# AD_3.net
KiCad netlist of a schematic drawn in Altium Designer
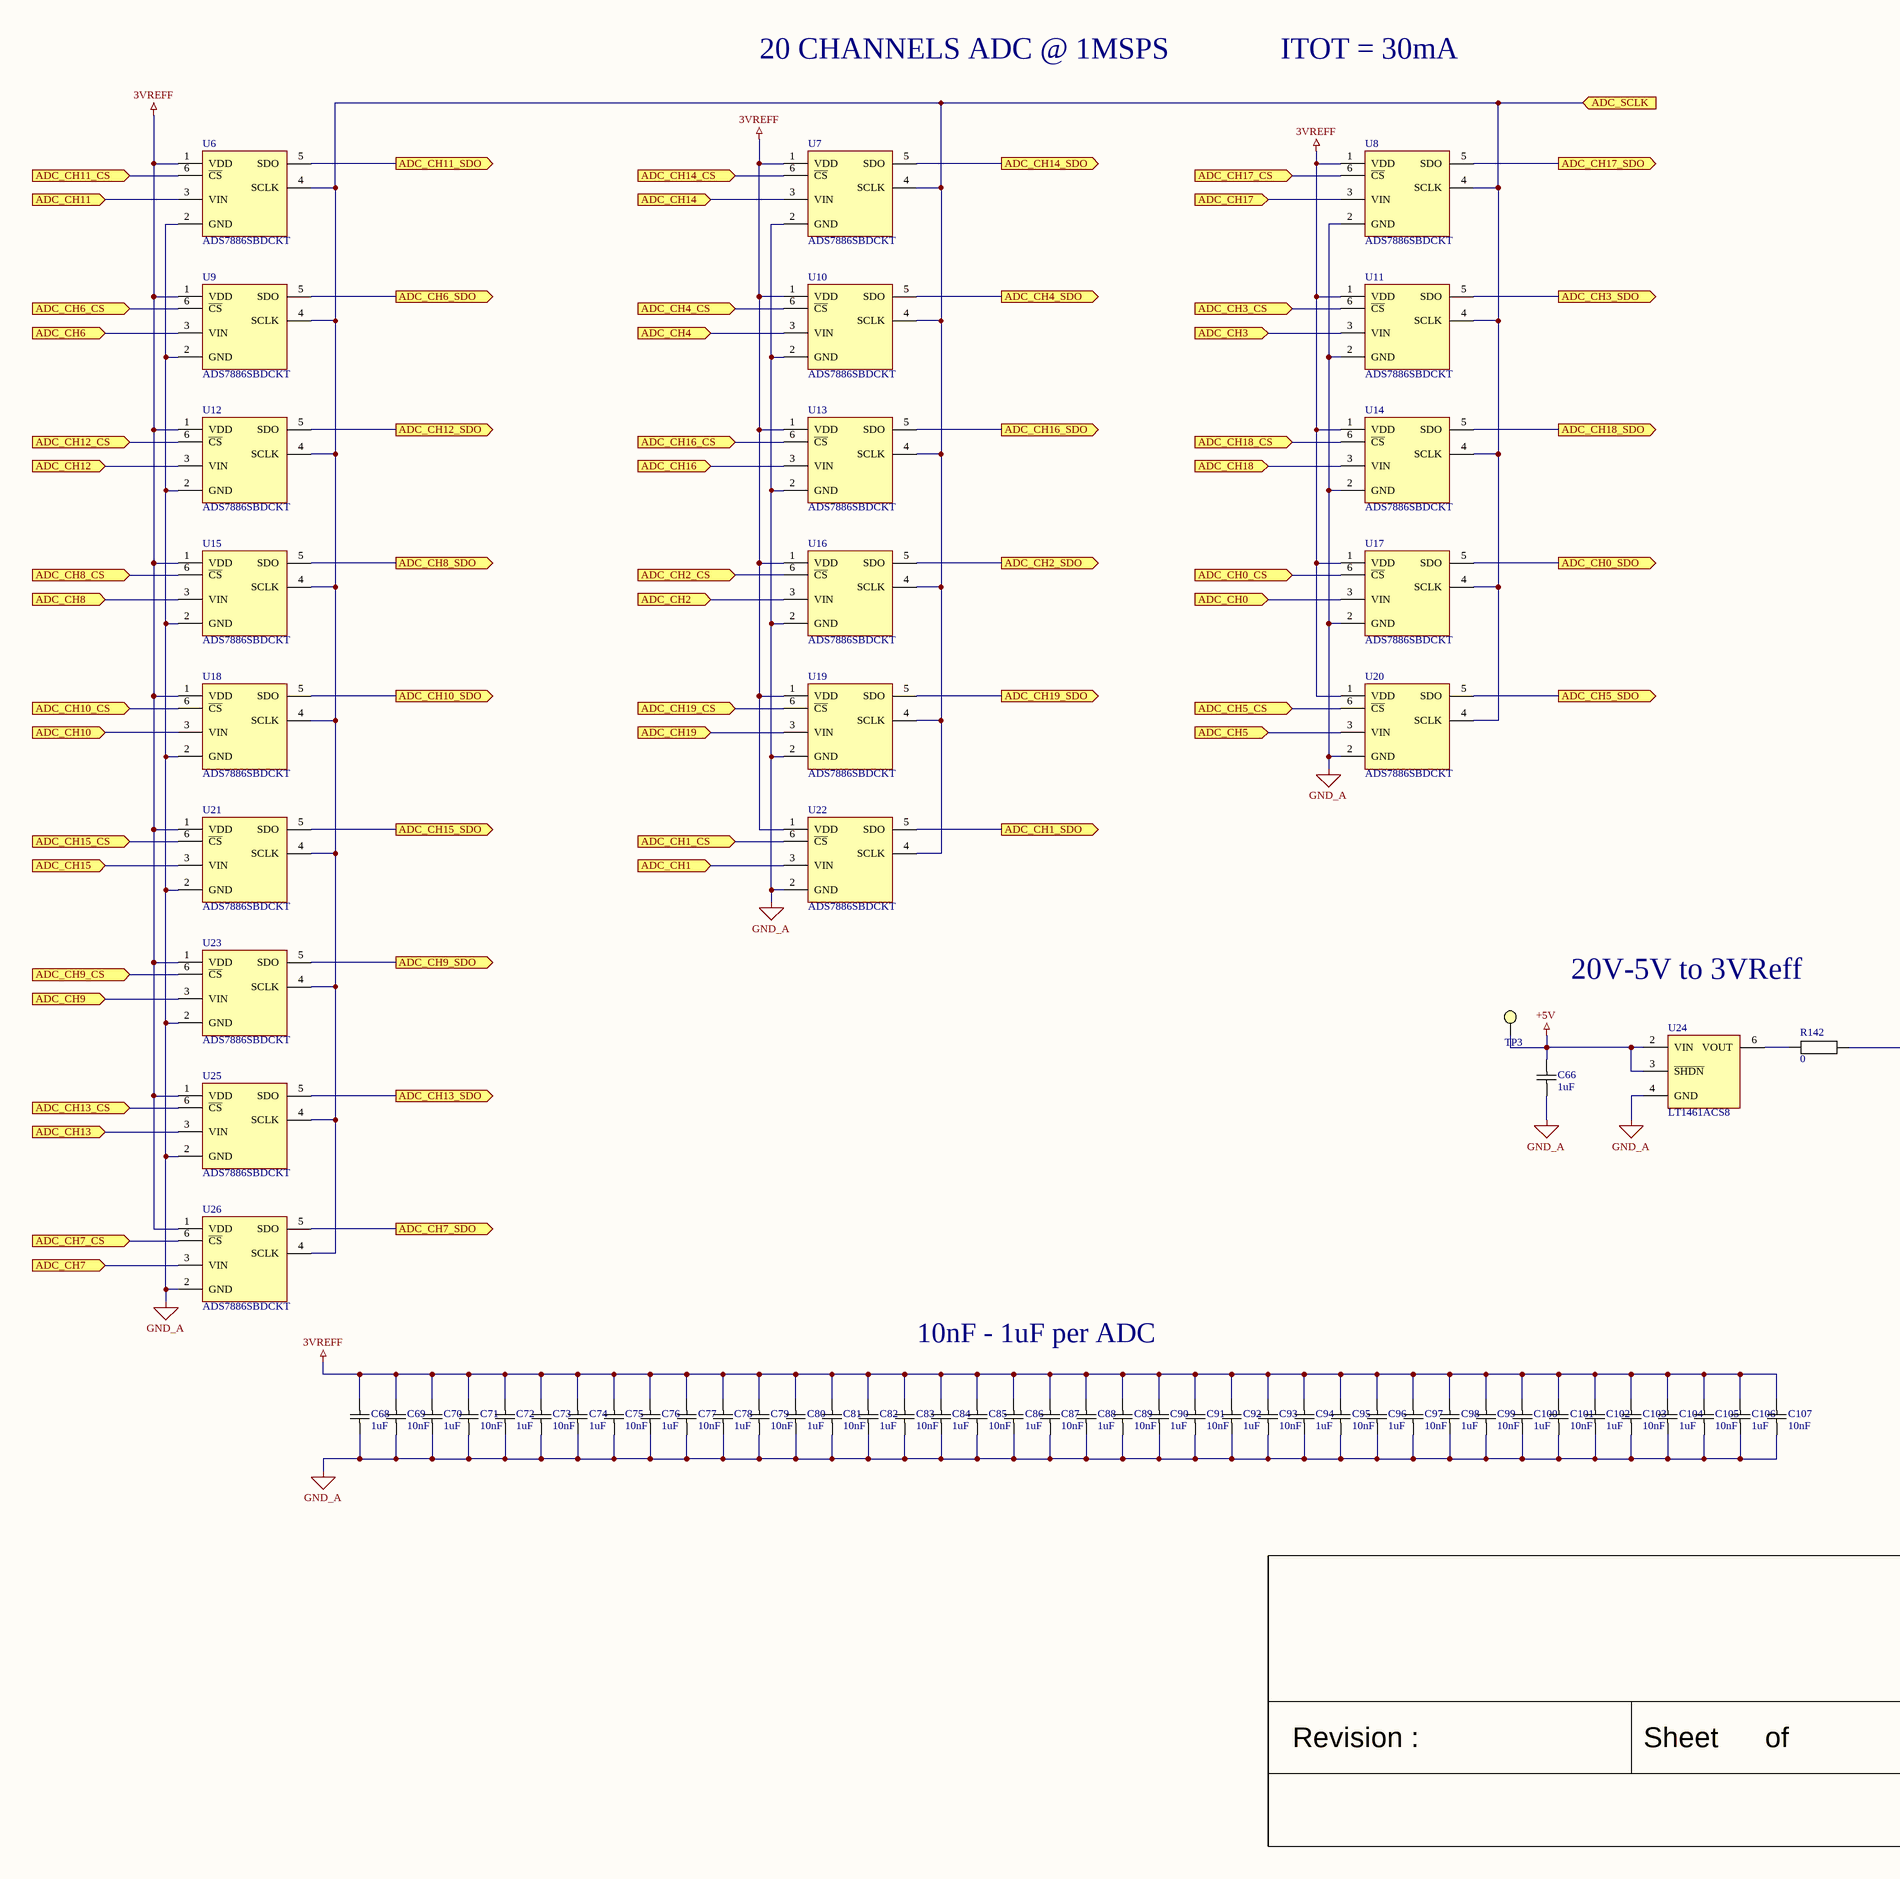
[diagram p0: AD_3.SchDoc, left]
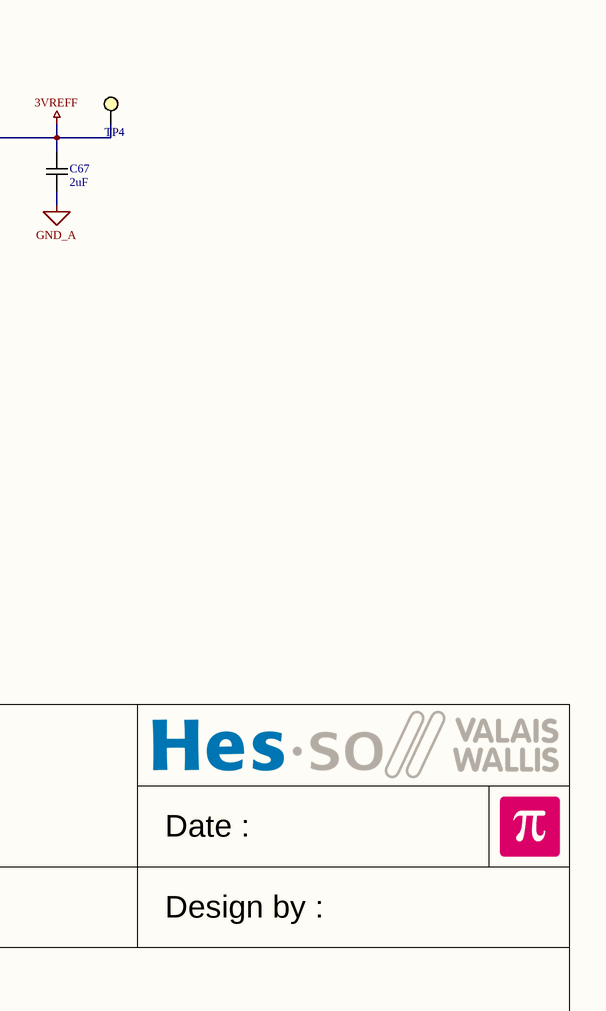
[diagram p1: AD_3.SchDoc, right]

(export (version "E")
  (design (tool "Eeschema 10.0.6"))
  (components
    (comp (ref "C66")
      (value "1uF")
      (footprint "CAPACITOR 1608 REFLOW")
      (description "Capacitor")
      (libsource (lib "Capacitor") (part "Capacitor"))
    )
    (comp (ref "C67")
      (value "2uF")
      (footprint "CAPACITOR 1608 REFLOW")
      (description "Capacitor")
      (libsource (lib "Capacitor") (part "Capacitor"))
    )
    (comp (ref "C68")
      (value "1uF")
      (footprint "CAPACITOR 1608 REFLOW")
      (description "Capacitor")
      (libsource (lib "Capacitor") (part "Capacitor"))
    )
    (comp (ref "C69")
      (value "10nF")
      (footprint "CAPACITOR 1608 REFLOW")
      (description "Capacitor")
      (libsource (lib "Capacitor") (part "Capacitor"))
    )
    (comp (ref "C70")
      (value "1uF")
      (footprint "CAPACITOR 1608 REFLOW")
      (description "Capacitor")
      (libsource (lib "Capacitor") (part "Capacitor"))
    )
    (comp (ref "C71")
      (value "10nF")
      (footprint "CAPACITOR 1608 REFLOW")
      (description "Capacitor")
      (libsource (lib "Capacitor") (part "Capacitor"))
    )
    (comp (ref "C72")
      (value "1uF")
      (footprint "CAPACITOR 1608 REFLOW")
      (description "Capacitor")
      (libsource (lib "Capacitor") (part "Capacitor"))
    )
    (comp (ref "C73")
      (value "10nF")
      (footprint "CAPACITOR 1608 REFLOW")
      (description "Capacitor")
      (libsource (lib "Capacitor") (part "Capacitor"))
    )
    (comp (ref "C74")
      (value "1uF")
      (footprint "CAPACITOR 1608 REFLOW")
      (description "Capacitor")
      (libsource (lib "Capacitor") (part "Capacitor"))
    )
    (comp (ref "C75")
      (value "10nF")
      (footprint "CAPACITOR 1608 REFLOW")
      (description "Capacitor")
      (libsource (lib "Capacitor") (part "Capacitor"))
    )
    (comp (ref "C76")
      (value "1uF")
      (footprint "CAPACITOR 1608 REFLOW")
      (description "Capacitor")
      (libsource (lib "Capacitor") (part "Capacitor"))
    )
    (comp (ref "C77")
      (value "10nF")
      (footprint "CAPACITOR 1608 REFLOW")
      (description "Capacitor")
      (libsource (lib "Capacitor") (part "Capacitor"))
    )
    (comp (ref "C78")
      (value "1uF")
      (footprint "CAPACITOR 1608 REFLOW")
      (description "Capacitor")
      (libsource (lib "Capacitor") (part "Capacitor"))
    )
    (comp (ref "C79")
      (value "10nF")
      (footprint "CAPACITOR 1608 REFLOW")
      (description "Capacitor")
      (libsource (lib "Capacitor") (part "Capacitor"))
    )
    (comp (ref "C80")
      (value "1uF")
      (footprint "CAPACITOR 1608 REFLOW")
      (description "Capacitor")
      (libsource (lib "Capacitor") (part "Capacitor"))
    )
    (comp (ref "C81")
      (value "10nF")
      (footprint "CAPACITOR 1608 REFLOW")
      (description "Capacitor")
      (libsource (lib "Capacitor") (part "Capacitor"))
    )
    (comp (ref "C82")
      (value "1uF")
      (footprint "CAPACITOR 1608 REFLOW")
      (description "Capacitor")
      (libsource (lib "Capacitor") (part "Capacitor"))
    )
    (comp (ref "C83")
      (value "10nF")
      (footprint "CAPACITOR 1608 REFLOW")
      (description "Capacitor")
      (libsource (lib "Capacitor") (part "Capacitor"))
    )
    (comp (ref "C84")
      (value "1uF")
      (footprint "CAPACITOR 1608 REFLOW")
      (description "Capacitor")
      (libsource (lib "Capacitor") (part "Capacitor"))
    )
    (comp (ref "C85")
      (value "10nF")
      (footprint "CAPACITOR 1608 REFLOW")
      (description "Capacitor")
      (libsource (lib "Capacitor") (part "Capacitor"))
    )
    (comp (ref "C86")
      (value "1uF")
      (footprint "CAPACITOR 1608 REFLOW")
      (description "Capacitor")
      (libsource (lib "Capacitor") (part "Capacitor"))
    )
    (comp (ref "C87")
      (value "10nF")
      (footprint "CAPACITOR 1608 REFLOW")
      (description "Capacitor")
      (libsource (lib "Capacitor") (part "Capacitor"))
    )
    (comp (ref "C88")
      (value "1uF")
      (footprint "CAPACITOR 1608 REFLOW")
      (description "Capacitor")
      (libsource (lib "Capacitor") (part "Capacitor"))
    )
    (comp (ref "C89")
      (value "10nF")
      (footprint "CAPACITOR 1608 REFLOW")
      (description "Capacitor")
      (libsource (lib "Capacitor") (part "Capacitor"))
    )
    (comp (ref "C90")
      (value "1uF")
      (footprint "CAPACITOR 1608 REFLOW")
      (description "Capacitor")
      (libsource (lib "Capacitor") (part "Capacitor"))
    )
    (comp (ref "C91")
      (value "10nF")
      (footprint "CAPACITOR 1608 REFLOW")
      (description "Capacitor")
      (libsource (lib "Capacitor") (part "Capacitor"))
    )
    (comp (ref "C92")
      (value "1uF")
      (footprint "CAPACITOR 1608 REFLOW")
      (description "Capacitor")
      (libsource (lib "Capacitor") (part "Capacitor"))
    )
    (comp (ref "C93")
      (value "10nF")
      (footprint "CAPACITOR 1608 REFLOW")
      (description "Capacitor")
      (libsource (lib "Capacitor") (part "Capacitor"))
    )
    (comp (ref "C94")
      (value "1uF")
      (footprint "CAPACITOR 1608 REFLOW")
      (description "Capacitor")
      (libsource (lib "Capacitor") (part "Capacitor"))
    )
    (comp (ref "C95")
      (value "10nF")
      (footprint "CAPACITOR 1608 REFLOW")
      (description "Capacitor")
      (libsource (lib "Capacitor") (part "Capacitor"))
    )
    (comp (ref "C96")
      (value "1uF")
      (footprint "CAPACITOR 1608 REFLOW")
      (description "Capacitor")
      (libsource (lib "Capacitor") (part "Capacitor"))
    )
    (comp (ref "C97")
      (value "10nF")
      (footprint "CAPACITOR 1608 REFLOW")
      (description "Capacitor")
      (libsource (lib "Capacitor") (part "Capacitor"))
    )
    (comp (ref "C98")
      (value "1uF")
      (footprint "CAPACITOR 1608 REFLOW")
      (description "Capacitor")
      (libsource (lib "Capacitor") (part "Capacitor"))
    )
    (comp (ref "C99")
      (value "10nF")
      (footprint "CAPACITOR 1608 REFLOW")
      (description "Capacitor")
      (libsource (lib "Capacitor") (part "Capacitor"))
    )
    (comp (ref "C100")
      (value "1uF")
      (footprint "CAPACITOR 1608 REFLOW")
      (description "Capacitor")
      (libsource (lib "Capacitor") (part "Capacitor"))
    )
    (comp (ref "C101")
      (value "10nF")
      (footprint "CAPACITOR 1608 REFLOW")
      (description "Capacitor")
      (libsource (lib "Capacitor") (part "Capacitor"))
    )
    (comp (ref "C102")
      (value "1uF")
      (footprint "CAPACITOR 1608 REFLOW")
      (description "Capacitor")
      (libsource (lib "Capacitor") (part "Capacitor"))
    )
    (comp (ref "C103")
      (value "10nF")
      (footprint "CAPACITOR 1608 REFLOW")
      (description "Capacitor")
      (libsource (lib "Capacitor") (part "Capacitor"))
    )
    (comp (ref "C104")
      (value "1uF")
      (footprint "CAPACITOR 1608 REFLOW")
      (description "Capacitor")
      (libsource (lib "Capacitor") (part "Capacitor"))
    )
    (comp (ref "C105")
      (value "10nF")
      (footprint "CAPACITOR 1608 REFLOW")
      (description "Capacitor")
      (libsource (lib "Capacitor") (part "Capacitor"))
    )
    (comp (ref "C106")
      (value "1uF")
      (footprint "CAPACITOR 1608 REFLOW")
      (description "Capacitor")
      (libsource (lib "Capacitor") (part "Capacitor"))
    )
    (comp (ref "C107")
      (value "10nF")
      (footprint "CAPACITOR 1608 REFLOW")
      (description "Capacitor")
      (libsource (lib "Capacitor") (part "Capacitor"))
    )
    (comp (ref "R142")
      (value "0")
      (footprint "RESISTOR 1608 REFLOW")
      (description "Resistor 1% 50V 100mW 1608(0603)")
      (libsource (lib "Resistor") (part "Resistor"))
    )
    (comp (ref "TP3")
      (value "*")
      (footprint "Test Point Keystone Miniature RED")
      (description "Test Point")
      (libsource (lib "Testpoint") (part "Test Point"))
    )
    (comp (ref "TP4")
      (value "*")
      (footprint "Test Point Keystone Miniature RED")
      (description "Test Point")
      (libsource (lib "Testpoint") (part "Test Point"))
    )
    (comp (ref "U6")
      (value "ADS7886SBDCKT")
      (footprint "SOT23-6 P0.95 C1.5x3.0 H1.3")
      (description "12-Bit, 1-MSPS, Micro-Power, Miniature SAR Analog-to-Digital Converters")
      (libsource (lib "Converter") (part "ADS7886SBDCKT"))
    )
    (comp (ref "U7")
      (value "ADS7886SBDCKT")
      (footprint "SOT23-6 P0.95 C1.5x3.0 H1.3")
      (description "12-Bit, 1-MSPS, Micro-Power, Miniature SAR Analog-to-Digital Converters")
      (libsource (lib "Converter") (part "ADS7886SBDCKT"))
    )
    (comp (ref "U8")
      (value "ADS7886SBDCKT")
      (footprint "SOT23-6 P0.95 C1.5x3.0 H1.3")
      (description "12-Bit, 1-MSPS, Micro-Power, Miniature SAR Analog-to-Digital Converters")
      (libsource (lib "Converter") (part "ADS7886SBDCKT"))
    )
    (comp (ref "U9")
      (value "ADS7886SBDCKT")
      (footprint "SOT23-6 P0.95 C1.5x3.0 H1.3")
      (description "12-Bit, 1-MSPS, Micro-Power, Miniature SAR Analog-to-Digital Converters")
      (libsource (lib "Converter") (part "ADS7886SBDCKT"))
    )
    (comp (ref "U10")
      (value "ADS7886SBDCKT")
      (footprint "SOT23-6 P0.95 C1.5x3.0 H1.3")
      (description "12-Bit, 1-MSPS, Micro-Power, Miniature SAR Analog-to-Digital Converters")
      (libsource (lib "Converter") (part "ADS7886SBDCKT"))
    )
    (comp (ref "U11")
      (value "ADS7886SBDCKT")
      (footprint "SOT23-6 P0.95 C1.5x3.0 H1.3")
      (description "12-Bit, 1-MSPS, Micro-Power, Miniature SAR Analog-to-Digital Converters")
      (libsource (lib "Converter") (part "ADS7886SBDCKT"))
    )
    (comp (ref "U12")
      (value "ADS7886SBDCKT")
      (footprint "SOT23-6 P0.95 C1.5x3.0 H1.3")
      (description "12-Bit, 1-MSPS, Micro-Power, Miniature SAR Analog-to-Digital Converters")
      (libsource (lib "Converter") (part "ADS7886SBDCKT"))
    )
    (comp (ref "U13")
      (value "ADS7886SBDCKT")
      (footprint "SOT23-6 P0.95 C1.5x3.0 H1.3")
      (description "12-Bit, 1-MSPS, Micro-Power, Miniature SAR Analog-to-Digital Converters")
      (libsource (lib "Converter") (part "ADS7886SBDCKT"))
    )
    (comp (ref "U14")
      (value "ADS7886SBDCKT")
      (footprint "SOT23-6 P0.95 C1.5x3.0 H1.3")
      (description "12-Bit, 1-MSPS, Micro-Power, Miniature SAR Analog-to-Digital Converters")
      (libsource (lib "Converter") (part "ADS7886SBDCKT"))
    )
    (comp (ref "U15")
      (value "ADS7886SBDCKT")
      (footprint "SOT23-6 P0.95 C1.5x3.0 H1.3")
      (description "12-Bit, 1-MSPS, Micro-Power, Miniature SAR Analog-to-Digital Converters")
      (libsource (lib "Converter") (part "ADS7886SBDCKT"))
    )
    (comp (ref "U16")
      (value "ADS7886SBDCKT")
      (footprint "SOT23-6 P0.95 C1.5x3.0 H1.3")
      (description "12-Bit, 1-MSPS, Micro-Power, Miniature SAR Analog-to-Digital Converters")
      (libsource (lib "Converter") (part "ADS7886SBDCKT"))
    )
    (comp (ref "U17")
      (value "ADS7886SBDCKT")
      (footprint "SOT23-6 P0.95 C1.5x3.0 H1.3")
      (description "12-Bit, 1-MSPS, Micro-Power, Miniature SAR Analog-to-Digital Converters")
      (libsource (lib "Converter") (part "ADS7886SBDCKT"))
    )
    (comp (ref "U18")
      (value "ADS7886SBDCKT")
      (footprint "SOT23-6 P0.95 C1.5x3.0 H1.3")
      (description "12-Bit, 1-MSPS, Micro-Power, Miniature SAR Analog-to-Digital Converters")
      (libsource (lib "Converter") (part "ADS7886SBDCKT"))
    )
    (comp (ref "U19")
      (value "ADS7886SBDCKT")
      (footprint "SOT23-6 P0.95 C1.5x3.0 H1.3")
      (description "12-Bit, 1-MSPS, Micro-Power, Miniature SAR Analog-to-Digital Converters")
      (libsource (lib "Converter") (part "ADS7886SBDCKT"))
    )
    (comp (ref "U20")
      (value "ADS7886SBDCKT")
      (footprint "SOT23-6 P0.95 C1.5x3.0 H1.3")
      (description "12-Bit, 1-MSPS, Micro-Power, Miniature SAR Analog-to-Digital Converters")
      (libsource (lib "Converter") (part "ADS7886SBDCKT"))
    )
    (comp (ref "U21")
      (value "ADS7886SBDCKT")
      (footprint "SOT23-6 P0.95 C1.5x3.0 H1.3")
      (description "12-Bit, 1-MSPS, Micro-Power, Miniature SAR Analog-to-Digital Converters")
      (libsource (lib "Converter") (part "ADS7886SBDCKT"))
    )
    (comp (ref "U22")
      (value "ADS7886SBDCKT")
      (footprint "SOT23-6 P0.95 C1.5x3.0 H1.3")
      (description "12-Bit, 1-MSPS, Micro-Power, Miniature SAR Analog-to-Digital Converters")
      (libsource (lib "Converter") (part "ADS7886SBDCKT"))
    )
    (comp (ref "U23")
      (value "ADS7886SBDCKT")
      (footprint "SOT23-6 P0.95 C1.5x3.0 H1.3")
      (description "12-Bit, 1-MSPS, Micro-Power, Miniature SAR Analog-to-Digital Converters")
      (libsource (lib "Converter") (part "ADS7886SBDCKT"))
    )
    (comp (ref "U24")
      (value "LT1461ACS8")
      (footprint "SO8 P1.27 C4.0X5.0 H1.75")
      (description "Micropower Precision Low Dropout Series Voltage Reference Family")
      (libsource (lib "Regulator") (part "LT1461ACS8"))
    )
    (comp (ref "U25")
      (value "ADS7886SBDCKT")
      (footprint "SOT23-6 P0.95 C1.5x3.0 H1.3")
      (description "12-Bit, 1-MSPS, Micro-Power, Miniature SAR Analog-to-Digital Converters")
      (libsource (lib "Converter") (part "ADS7886SBDCKT"))
    )
    (comp (ref "U26")
      (value "ADS7886SBDCKT")
      (footprint "SOT23-6 P0.95 C1.5x3.0 H1.3")
      (description "12-Bit, 1-MSPS, Micro-Power, Miniature SAR Analog-to-Digital Converters")
      (libsource (lib "Converter") (part "ADS7886SBDCKT"))
    )
  )
  (nets
    (net (code "1") (name "+5V") (class "Default")
      (node (ref "C66") (pin "2") (pinfunction "2_2") (pintype "passive"))
      (node (ref "TP3") (pin "1") (pinfunction "1_1") (pintype "passive"))
      (node (ref "U24") (pin "2") (pinfunction "VIN_2") (pintype "passive"))
      (node (ref "U24") (pin "3") (pinfunction "~{SHDN}_3") (pintype "passive"))
    )
    (net (code "2") (name "/ADC_CH0") (class "Default")
      (node (ref "U17") (pin "3") (pinfunction "VIN_3") (pintype "passive"))
    )
    (net (code "3") (name "/ADC_CH0_CS") (class "Default")
      (node (ref "U17") (pin "6") (pinfunction "~{CS}_6") (pintype "passive"))
    )
    (net (code "4") (name "/ADC_CH0_SDO") (class "Default")
      (node (ref "U17") (pin "5") (pinfunction "SDO_5") (pintype "passive"))
    )
    (net (code "5") (name "/ADC_CH1") (class "Default")
      (node (ref "U22") (pin "3") (pinfunction "VIN_3") (pintype "passive"))
    )
    (net (code "6") (name "/ADC_CH1_CS") (class "Default")
      (node (ref "U22") (pin "6") (pinfunction "~{CS}_6") (pintype "passive"))
    )
    (net (code "7") (name "/ADC_CH1_SDO") (class "Default")
      (node (ref "U22") (pin "5") (pinfunction "SDO_5") (pintype "passive"))
    )
    (net (code "8") (name "/ADC_CH2") (class "Default")
      (node (ref "U16") (pin "3") (pinfunction "VIN_3") (pintype "passive"))
    )
    (net (code "9") (name "/ADC_CH2_CS") (class "Default")
      (node (ref "U16") (pin "6") (pinfunction "~{CS}_6") (pintype "passive"))
    )
    (net (code "10") (name "/ADC_CH2_SDO") (class "Default")
      (node (ref "U16") (pin "5") (pinfunction "SDO_5") (pintype "passive"))
    )
    (net (code "11") (name "/ADC_CH3") (class "Default")
      (node (ref "U11") (pin "3") (pinfunction "VIN_3") (pintype "passive"))
    )
    (net (code "12") (name "/ADC_CH3_CS") (class "Default")
      (node (ref "U11") (pin "6") (pinfunction "~{CS}_6") (pintype "passive"))
    )
    (net (code "13") (name "/ADC_CH3_SDO") (class "Default")
      (node (ref "U11") (pin "5") (pinfunction "SDO_5") (pintype "passive"))
    )
    (net (code "14") (name "/ADC_CH4") (class "Default")
      (node (ref "U10") (pin "3") (pinfunction "VIN_3") (pintype "passive"))
    )
    (net (code "15") (name "/ADC_CH4_CS") (class "Default")
      (node (ref "U10") (pin "6") (pinfunction "~{CS}_6") (pintype "passive"))
    )
    (net (code "16") (name "/ADC_CH4_SDO") (class "Default")
      (node (ref "U10") (pin "5") (pinfunction "SDO_5") (pintype "passive"))
    )
    (net (code "17") (name "/ADC_CH5") (class "Default")
      (node (ref "U20") (pin "3") (pinfunction "VIN_3") (pintype "passive"))
    )
    (net (code "18") (name "/ADC_CH5_CS") (class "Default")
      (node (ref "U20") (pin "6") (pinfunction "~{CS}_6") (pintype "passive"))
    )
    (net (code "19") (name "/ADC_CH5_SDO") (class "Default")
      (node (ref "U20") (pin "5") (pinfunction "SDO_5") (pintype "passive"))
    )
    (net (code "20") (name "/ADC_CH6") (class "Default")
      (node (ref "U9") (pin "3") (pinfunction "VIN_3") (pintype "passive"))
    )
    (net (code "21") (name "/ADC_CH6_CS") (class "Default")
      (node (ref "U9") (pin "6") (pinfunction "~{CS}_6") (pintype "passive"))
    )
    (net (code "22") (name "/ADC_CH6_SDO") (class "Default")
      (node (ref "U9") (pin "5") (pinfunction "SDO_5") (pintype "passive"))
    )
    (net (code "23") (name "/ADC_CH7") (class "Default")
      (node (ref "U26") (pin "3") (pinfunction "VIN_3") (pintype "passive"))
    )
    (net (code "24") (name "/ADC_CH7_CS") (class "Default")
      (node (ref "U26") (pin "6") (pinfunction "~{CS}_6") (pintype "passive"))
    )
    (net (code "25") (name "/ADC_CH7_SDO") (class "Default")
      (node (ref "U26") (pin "5") (pinfunction "SDO_5") (pintype "passive"))
    )
    (net (code "26") (name "/ADC_CH8") (class "Default")
      (node (ref "U15") (pin "3") (pinfunction "VIN_3") (pintype "passive"))
    )
    (net (code "27") (name "/ADC_CH8_CS") (class "Default")
      (node (ref "U15") (pin "6") (pinfunction "~{CS}_6") (pintype "passive"))
    )
    (net (code "28") (name "/ADC_CH8_SDO") (class "Default")
      (node (ref "U15") (pin "5") (pinfunction "SDO_5") (pintype "passive"))
    )
    (net (code "29") (name "/ADC_CH9") (class "Default")
      (node (ref "U23") (pin "3") (pinfunction "VIN_3") (pintype "passive"))
    )
    (net (code "30") (name "/ADC_CH9_CS") (class "Default")
      (node (ref "U23") (pin "6") (pinfunction "~{CS}_6") (pintype "passive"))
    )
    (net (code "31") (name "/ADC_CH9_SDO") (class "Default")
      (node (ref "U23") (pin "5") (pinfunction "SDO_5") (pintype "passive"))
    )
    (net (code "32") (name "/ADC_CH10") (class "Default")
      (node (ref "U18") (pin "3") (pinfunction "VIN_3") (pintype "passive"))
    )
    (net (code "33") (name "/ADC_CH10_CS") (class "Default")
      (node (ref "U18") (pin "6") (pinfunction "~{CS}_6") (pintype "passive"))
    )
    (net (code "34") (name "/ADC_CH10_SDO") (class "Default")
      (node (ref "U18") (pin "5") (pinfunction "SDO_5") (pintype "passive"))
    )
    (net (code "35") (name "/ADC_CH11") (class "Default")
      (node (ref "U6") (pin "3") (pinfunction "VIN_3") (pintype "passive"))
    )
    (net (code "36") (name "/ADC_CH11_CS") (class "Default")
      (node (ref "U6") (pin "6") (pinfunction "~{CS}_6") (pintype "passive"))
    )
    (net (code "37") (name "/ADC_CH11_SDO") (class "Default")
      (node (ref "U6") (pin "5") (pinfunction "SDO_5") (pintype "passive"))
    )
    (net (code "38") (name "/ADC_CH12") (class "Default")
      (node (ref "U12") (pin "3") (pinfunction "VIN_3") (pintype "passive"))
    )
    (net (code "39") (name "/ADC_CH12_CS") (class "Default")
      (node (ref "U12") (pin "6") (pinfunction "~{CS}_6") (pintype "passive"))
    )
    (net (code "40") (name "/ADC_CH12_SDO") (class "Default")
      (node (ref "U12") (pin "5") (pinfunction "SDO_5") (pintype "passive"))
    )
    (net (code "41") (name "/ADC_CH13") (class "Default")
      (node (ref "U25") (pin "3") (pinfunction "VIN_3") (pintype "passive"))
    )
    (net (code "42") (name "/ADC_CH13_CS") (class "Default")
      (node (ref "U25") (pin "6") (pinfunction "~{CS}_6") (pintype "passive"))
    )
    (net (code "43") (name "/ADC_CH13_SDO") (class "Default")
      (node (ref "U25") (pin "5") (pinfunction "SDO_5") (pintype "passive"))
    )
    (net (code "44") (name "/ADC_CH14") (class "Default")
      (node (ref "U7") (pin "3") (pinfunction "VIN_3") (pintype "passive"))
    )
    (net (code "45") (name "/ADC_CH14_CS") (class "Default")
      (node (ref "U7") (pin "6") (pinfunction "~{CS}_6") (pintype "passive"))
    )
    (net (code "46") (name "/ADC_CH14_SDO") (class "Default")
      (node (ref "U7") (pin "5") (pinfunction "SDO_5") (pintype "passive"))
    )
    (net (code "47") (name "/ADC_CH15") (class "Default")
      (node (ref "U21") (pin "3") (pinfunction "VIN_3") (pintype "passive"))
    )
    (net (code "48") (name "/ADC_CH15_CS") (class "Default")
      (node (ref "U21") (pin "6") (pinfunction "~{CS}_6") (pintype "passive"))
    )
    (net (code "49") (name "/ADC_CH15_SDO") (class "Default")
      (node (ref "U21") (pin "5") (pinfunction "SDO_5") (pintype "passive"))
    )
    (net (code "50") (name "/ADC_CH16") (class "Default")
      (node (ref "U13") (pin "3") (pinfunction "VIN_3") (pintype "passive"))
    )
    (net (code "51") (name "/ADC_CH16_CS") (class "Default")
      (node (ref "U13") (pin "6") (pinfunction "~{CS}_6") (pintype "passive"))
    )
    (net (code "52") (name "/ADC_CH16_SDO") (class "Default")
      (node (ref "U13") (pin "5") (pinfunction "SDO_5") (pintype "passive"))
    )
    (net (code "53") (name "/ADC_CH17") (class "Default")
      (node (ref "U8") (pin "3") (pinfunction "VIN_3") (pintype "passive"))
    )
    (net (code "54") (name "/ADC_CH17_CS") (class "Default")
      (node (ref "U8") (pin "6") (pinfunction "~{CS}_6") (pintype "passive"))
    )
    (net (code "55") (name "/ADC_CH17_SDO") (class "Default")
      (node (ref "U8") (pin "5") (pinfunction "SDO_5") (pintype "passive"))
    )
    (net (code "56") (name "/ADC_CH18") (class "Default")
      (node (ref "U14") (pin "3") (pinfunction "VIN_3") (pintype "passive"))
    )
    (net (code "57") (name "/ADC_CH18_CS") (class "Default")
      (node (ref "U14") (pin "6") (pinfunction "~{CS}_6") (pintype "passive"))
    )
    (net (code "58") (name "/ADC_CH18_SDO") (class "Default")
      (node (ref "U14") (pin "5") (pinfunction "SDO_5") (pintype "passive"))
    )
    (net (code "59") (name "/ADC_CH19") (class "Default")
      (node (ref "U19") (pin "3") (pinfunction "VIN_3") (pintype "passive"))
    )
    (net (code "60") (name "/ADC_CH19_CS") (class "Default")
      (node (ref "U19") (pin "6") (pinfunction "~{CS}_6") (pintype "passive"))
    )
    (net (code "61") (name "/ADC_CH19_SDO") (class "Default")
      (node (ref "U19") (pin "5") (pinfunction "SDO_5") (pintype "passive"))
    )
    (net (code "62") (name "/ADC_SCLK") (class "Default")
      (node (ref "U10") (pin "4") (pinfunction "SCLK_4") (pintype "passive"))
      (node (ref "U11") (pin "4") (pinfunction "SCLK_4") (pintype "passive"))
      (node (ref "U12") (pin "4") (pinfunction "SCLK_4") (pintype "passive"))
      (node (ref "U13") (pin "4") (pinfunction "SCLK_4") (pintype "passive"))
      (node (ref "U14") (pin "4") (pinfunction "SCLK_4") (pintype "passive"))
      (node (ref "U15") (pin "4") (pinfunction "SCLK_4") (pintype "passive"))
      (node (ref "U16") (pin "4") (pinfunction "SCLK_4") (pintype "passive"))
      (node (ref "U17") (pin "4") (pinfunction "SCLK_4") (pintype "passive"))
      (node (ref "U18") (pin "4") (pinfunction "SCLK_4") (pintype "passive"))
      (node (ref "U19") (pin "4") (pinfunction "SCLK_4") (pintype "passive"))
      (node (ref "U20") (pin "4") (pinfunction "SCLK_4") (pintype "passive"))
      (node (ref "U21") (pin "4") (pinfunction "SCLK_4") (pintype "passive"))
      (node (ref "U22") (pin "4") (pinfunction "SCLK_4") (pintype "passive"))
      (node (ref "U23") (pin "4") (pinfunction "SCLK_4") (pintype "passive"))
      (node (ref "U25") (pin "4") (pinfunction "SCLK_4") (pintype "passive"))
      (node (ref "U26") (pin "4") (pinfunction "SCLK_4") (pintype "passive"))
      (node (ref "U6") (pin "4") (pinfunction "SCLK_4") (pintype "passive"))
      (node (ref "U7") (pin "4") (pinfunction "SCLK_4") (pintype "passive"))
      (node (ref "U8") (pin "4") (pinfunction "SCLK_4") (pintype "passive"))
      (node (ref "U9") (pin "4") (pinfunction "SCLK_4") (pintype "passive"))
    )
    (net (code "63") (name "3VREFF") (class "Default")
      (node (ref "C100") (pin "2") (pinfunction "2_2") (pintype "passive"))
      (node (ref "C101") (pin "2") (pinfunction "2_2") (pintype "passive"))
      (node (ref "C102") (pin "2") (pinfunction "2_2") (pintype "passive"))
      (node (ref "C103") (pin "2") (pinfunction "2_2") (pintype "passive"))
      (node (ref "C104") (pin "2") (pinfunction "2_2") (pintype "passive"))
      (node (ref "C105") (pin "2") (pinfunction "2_2") (pintype "passive"))
      (node (ref "C106") (pin "2") (pinfunction "2_2") (pintype "passive"))
      (node (ref "C107") (pin "2") (pinfunction "2_2") (pintype "passive"))
      (node (ref "C67") (pin "2") (pinfunction "2_2") (pintype "passive"))
      (node (ref "C68") (pin "2") (pinfunction "2_2") (pintype "passive"))
      (node (ref "C69") (pin "2") (pinfunction "2_2") (pintype "passive"))
      (node (ref "C70") (pin "2") (pinfunction "2_2") (pintype "passive"))
      (node (ref "C71") (pin "2") (pinfunction "2_2") (pintype "passive"))
      (node (ref "C72") (pin "2") (pinfunction "2_2") (pintype "passive"))
      (node (ref "C73") (pin "2") (pinfunction "2_2") (pintype "passive"))
      (node (ref "C74") (pin "2") (pinfunction "2_2") (pintype "passive"))
      (node (ref "C75") (pin "2") (pinfunction "2_2") (pintype "passive"))
      (node (ref "C76") (pin "2") (pinfunction "2_2") (pintype "passive"))
      (node (ref "C77") (pin "2") (pinfunction "2_2") (pintype "passive"))
      (node (ref "C78") (pin "2") (pinfunction "2_2") (pintype "passive"))
      (node (ref "C79") (pin "2") (pinfunction "2_2") (pintype "passive"))
      (node (ref "C80") (pin "2") (pinfunction "2_2") (pintype "passive"))
      (node (ref "C81") (pin "2") (pinfunction "2_2") (pintype "passive"))
      (node (ref "C82") (pin "2") (pinfunction "2_2") (pintype "passive"))
      (node (ref "C83") (pin "2") (pinfunction "2_2") (pintype "passive"))
      (node (ref "C84") (pin "2") (pinfunction "2_2") (pintype "passive"))
      (node (ref "C85") (pin "2") (pinfunction "2_2") (pintype "passive"))
      (node (ref "C86") (pin "2") (pinfunction "2_2") (pintype "passive"))
      (node (ref "C87") (pin "2") (pinfunction "2_2") (pintype "passive"))
      (node (ref "C88") (pin "2") (pinfunction "2_2") (pintype "passive"))
      (node (ref "C89") (pin "2") (pinfunction "2_2") (pintype "passive"))
      (node (ref "C90") (pin "2") (pinfunction "2_2") (pintype "passive"))
      (node (ref "C91") (pin "2") (pinfunction "2_2") (pintype "passive"))
      (node (ref "C92") (pin "2") (pinfunction "2_2") (pintype "passive"))
      (node (ref "C93") (pin "2") (pinfunction "2_2") (pintype "passive"))
      (node (ref "C94") (pin "2") (pinfunction "2_2") (pintype "passive"))
      (node (ref "C95") (pin "2") (pinfunction "2_2") (pintype "passive"))
      (node (ref "C96") (pin "2") (pinfunction "2_2") (pintype "passive"))
      (node (ref "C97") (pin "2") (pinfunction "2_2") (pintype "passive"))
      (node (ref "C98") (pin "2") (pinfunction "2_2") (pintype "passive"))
      (node (ref "C99") (pin "2") (pinfunction "2_2") (pintype "passive"))
      (node (ref "R142") (pin "2") (pinfunction "2_2") (pintype "passive"))
      (node (ref "TP4") (pin "1") (pinfunction "1_1") (pintype "passive"))
      (node (ref "U10") (pin "1") (pinfunction "VDD_1") (pintype "passive"))
      (node (ref "U11") (pin "1") (pinfunction "VDD_1") (pintype "passive"))
      (node (ref "U12") (pin "1") (pinfunction "VDD_1") (pintype "passive"))
      (node (ref "U13") (pin "1") (pinfunction "VDD_1") (pintype "passive"))
      (node (ref "U14") (pin "1") (pinfunction "VDD_1") (pintype "passive"))
      (node (ref "U15") (pin "1") (pinfunction "VDD_1") (pintype "passive"))
      (node (ref "U16") (pin "1") (pinfunction "VDD_1") (pintype "passive"))
      (node (ref "U17") (pin "1") (pinfunction "VDD_1") (pintype "passive"))
      (node (ref "U18") (pin "1") (pinfunction "VDD_1") (pintype "passive"))
      (node (ref "U19") (pin "1") (pinfunction "VDD_1") (pintype "passive"))
      (node (ref "U20") (pin "1") (pinfunction "VDD_1") (pintype "passive"))
      (node (ref "U21") (pin "1") (pinfunction "VDD_1") (pintype "passive"))
      (node (ref "U22") (pin "1") (pinfunction "VDD_1") (pintype "passive"))
      (node (ref "U23") (pin "1") (pinfunction "VDD_1") (pintype "passive"))
      (node (ref "U25") (pin "1") (pinfunction "VDD_1") (pintype "passive"))
      (node (ref "U26") (pin "1") (pinfunction "VDD_1") (pintype "passive"))
      (node (ref "U6") (pin "1") (pinfunction "VDD_1") (pintype "passive"))
      (node (ref "U7") (pin "1") (pinfunction "VDD_1") (pintype "passive"))
      (node (ref "U8") (pin "1") (pinfunction "VDD_1") (pintype "passive"))
      (node (ref "U9") (pin "1") (pinfunction "VDD_1") (pintype "passive"))
    )
    (net (code "64") (name "GND_A") (class "Default")
      (node (ref "C100") (pin "1") (pinfunction "1_1") (pintype "passive"))
      (node (ref "C101") (pin "1") (pinfunction "1_1") (pintype "passive"))
      (node (ref "C102") (pin "1") (pinfunction "1_1") (pintype "passive"))
      (node (ref "C103") (pin "1") (pinfunction "1_1") (pintype "passive"))
      (node (ref "C104") (pin "1") (pinfunction "1_1") (pintype "passive"))
      (node (ref "C105") (pin "1") (pinfunction "1_1") (pintype "passive"))
      (node (ref "C106") (pin "1") (pinfunction "1_1") (pintype "passive"))
      (node (ref "C107") (pin "1") (pinfunction "1_1") (pintype "passive"))
      (node (ref "C66") (pin "1") (pinfunction "1_1") (pintype "passive"))
      (node (ref "C67") (pin "1") (pinfunction "1_1") (pintype "passive"))
      (node (ref "C68") (pin "1") (pinfunction "1_1") (pintype "passive"))
      (node (ref "C69") (pin "1") (pinfunction "1_1") (pintype "passive"))
      (node (ref "C70") (pin "1") (pinfunction "1_1") (pintype "passive"))
      (node (ref "C71") (pin "1") (pinfunction "1_1") (pintype "passive"))
      (node (ref "C72") (pin "1") (pinfunction "1_1") (pintype "passive"))
      (node (ref "C73") (pin "1") (pinfunction "1_1") (pintype "passive"))
      (node (ref "C74") (pin "1") (pinfunction "1_1") (pintype "passive"))
      (node (ref "C75") (pin "1") (pinfunction "1_1") (pintype "passive"))
      (node (ref "C76") (pin "1") (pinfunction "1_1") (pintype "passive"))
      (node (ref "C77") (pin "1") (pinfunction "1_1") (pintype "passive"))
      (node (ref "C78") (pin "1") (pinfunction "1_1") (pintype "passive"))
      (node (ref "C79") (pin "1") (pinfunction "1_1") (pintype "passive"))
      (node (ref "C80") (pin "1") (pinfunction "1_1") (pintype "passive"))
      (node (ref "C81") (pin "1") (pinfunction "1_1") (pintype "passive"))
      (node (ref "C82") (pin "1") (pinfunction "1_1") (pintype "passive"))
      (node (ref "C83") (pin "1") (pinfunction "1_1") (pintype "passive"))
      (node (ref "C84") (pin "1") (pinfunction "1_1") (pintype "passive"))
      (node (ref "C85") (pin "1") (pinfunction "1_1") (pintype "passive"))
      (node (ref "C86") (pin "1") (pinfunction "1_1") (pintype "passive"))
      (node (ref "C87") (pin "1") (pinfunction "1_1") (pintype "passive"))
      (node (ref "C88") (pin "1") (pinfunction "1_1") (pintype "passive"))
      (node (ref "C89") (pin "1") (pinfunction "1_1") (pintype "passive"))
      (node (ref "C90") (pin "1") (pinfunction "1_1") (pintype "passive"))
      (node (ref "C91") (pin "1") (pinfunction "1_1") (pintype "passive"))
      (node (ref "C92") (pin "1") (pinfunction "1_1") (pintype "passive"))
      (node (ref "C93") (pin "1") (pinfunction "1_1") (pintype "passive"))
      (node (ref "C94") (pin "1") (pinfunction "1_1") (pintype "passive"))
      (node (ref "C95") (pin "1") (pinfunction "1_1") (pintype "passive"))
      (node (ref "C96") (pin "1") (pinfunction "1_1") (pintype "passive"))
      (node (ref "C97") (pin "1") (pinfunction "1_1") (pintype "passive"))
      (node (ref "C98") (pin "1") (pinfunction "1_1") (pintype "passive"))
      (node (ref "C99") (pin "1") (pinfunction "1_1") (pintype "passive"))
      (node (ref "U10") (pin "2") (pinfunction "GND_2") (pintype "passive"))
      (node (ref "U11") (pin "2") (pinfunction "GND_2") (pintype "passive"))
      (node (ref "U12") (pin "2") (pinfunction "GND_2") (pintype "passive"))
      (node (ref "U13") (pin "2") (pinfunction "GND_2") (pintype "passive"))
      (node (ref "U14") (pin "2") (pinfunction "GND_2") (pintype "passive"))
      (node (ref "U15") (pin "2") (pinfunction "GND_2") (pintype "passive"))
      (node (ref "U16") (pin "2") (pinfunction "GND_2") (pintype "passive"))
      (node (ref "U17") (pin "2") (pinfunction "GND_2") (pintype "passive"))
      (node (ref "U18") (pin "2") (pinfunction "GND_2") (pintype "passive"))
      (node (ref "U19") (pin "2") (pinfunction "GND_2") (pintype "passive"))
      (node (ref "U20") (pin "2") (pinfunction "GND_2") (pintype "passive"))
      (node (ref "U21") (pin "2") (pinfunction "GND_2") (pintype "passive"))
      (node (ref "U22") (pin "2") (pinfunction "GND_2") (pintype "passive"))
      (node (ref "U23") (pin "2") (pinfunction "GND_2") (pintype "passive"))
      (node (ref "U24") (pin "4") (pinfunction "GND_4") (pintype "passive"))
      (node (ref "U25") (pin "2") (pinfunction "GND_2") (pintype "passive"))
      (node (ref "U26") (pin "2") (pinfunction "GND_2") (pintype "passive"))
      (node (ref "U6") (pin "2") (pinfunction "GND_2") (pintype "passive"))
      (node (ref "U7") (pin "2") (pinfunction "GND_2") (pintype "passive"))
      (node (ref "U8") (pin "2") (pinfunction "GND_2") (pintype "passive"))
      (node (ref "U9") (pin "2") (pinfunction "GND_2") (pintype "passive"))
    )
    (net (code "65") (name "Net-(U24-VOUT)") (class "Default")
      (node (ref "R142") (pin "1") (pinfunction "1_1") (pintype "passive"))
      (node (ref "U24") (pin "6") (pinfunction "VOUT_6") (pintype "passive"))
    )
  )
)
